# PROC099A_SOP_Headers_Reference.net
KiCad netlist of a schematic drawn in Altium Designer
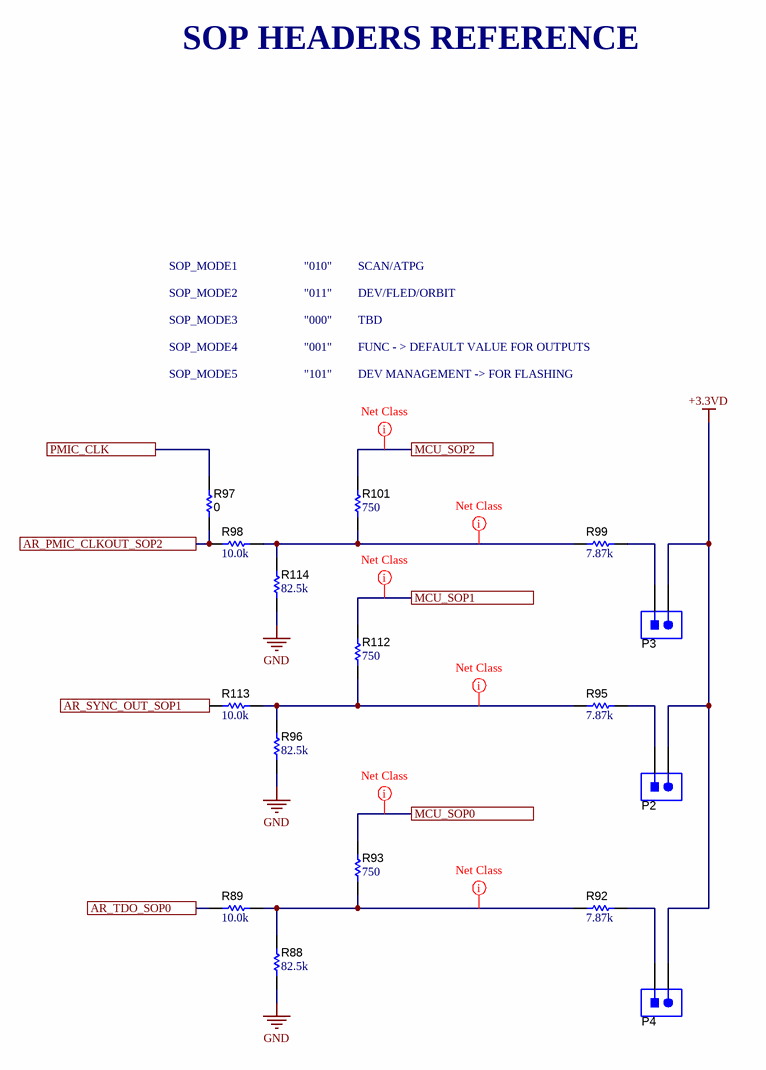
[diagram p0: PROC099A_SOP_Headers_Reference.SchDoc]

(export (version "E")
  (design (tool "Eeschema 10.0.6"))
  (components
    (comp (ref "P2")
      (value "TSW-102-07-G-S")
      (footprint "TSW-102-07-G-S")
      (description "Header, 100mil, 2x1, Gold, TH")
      (fields (field (name "MANUFACTURER") "Samtec"))
      (libsource (lib "Altium Vault - TI") (part "CMP-0075405-2"))
    )
    (comp (ref "P3")
      (value "TSW-102-07-G-S")
      (footprint "TSW-102-07-G-S")
      (description "Header, 100mil, 2x1, Gold, TH")
      (fields (field (name "MANUFACTURER") "Samtec"))
      (libsource (lib "Altium Vault - TI") (part "CMP-0075405-2"))
    )
    (comp (ref "P4")
      (value "TSW-102-07-G-S")
      (footprint "TSW-102-07-G-S")
      (description "Header, 100mil, 2x1, Gold, TH")
      (fields (field (name "MANUFACTURER") "Samtec"))
      (libsource (lib "Altium Vault - TI") (part "CMP-0075405-2"))
    )
    (comp (ref "R88")
      (value "CRCW040282K5FKED")
      (footprint "0402L")
      (description "RES, 82.5 k, 1%, 0.063 W, AEC-Q200 Grade 0, 0402")
      (fields (field (name "MANUFACTURER") "Vishay-Dale") (field (name "VALUEDISPLAYED") "82.5k"))
      (libsource (lib "Altium Vault - TI") (part "Resistor"))
    )
    (comp (ref "R89")
      (value "CRCW040210K0FKED")
      (footprint "0402L")
      (description "RES, 10.0 k, 1%, 0.063 W, AEC-Q200 Grade 0, 0402")
      (fields (field (name "MANUFACTURER") "Vishay-Dale") (field (name "VALUEDISPLAYED") "10.0k"))
      (libsource (lib "Altium Vault - TI") (part "CMP-0025958-3"))
    )
    (comp (ref "R92")
      (value "CRCW04027K87FKED")
      (footprint "0402L")
      (description "RES, 7.87 k, 1%, 0.063 W, AEC-Q200 Grade 0, 0402")
      (fields (field (name "MANUFACTURER") "Vishay-Dale") (field (name "VALUEDISPLAYED") "7.87k"))
      (libsource (lib "Altium Vault - TI") (part "Resistor"))
    )
    (comp (ref "R93")
      (value "CRCW0402750RFKED")
      (footprint "0402L")
      (description "RES, 750, 1%, 0.063 W, AEC-Q200 Grade 0, 0402")
      (fields (field (name "MANUFACTURER") "Vishay-Dale") (field (name "VALUEDISPLAYED") "750"))
      (libsource (lib "Altium Vault - TI") (part "Resistor"))
    )
    (comp (ref "R95")
      (value "CRCW04027K87FKED")
      (footprint "0402L")
      (description "RES, 7.87 k, 1%, 0.063 W, AEC-Q200 Grade 0, 0402")
      (fields (field (name "MANUFACTURER") "Vishay-Dale") (field (name "VALUEDISPLAYED") "7.87k"))
      (libsource (lib "Altium Vault - TI") (part "Resistor"))
    )
    (comp (ref "R96")
      (value "CRCW040282K5FKED")
      (footprint "0402L")
      (description "RES, 82.5 k, 1%, 0.063 W, AEC-Q200 Grade 0, 0402")
      (fields (field (name "MANUFACTURER") "Vishay-Dale") (field (name "VALUEDISPLAYED") "82.5k"))
      (libsource (lib "Altium Vault - TI") (part "Resistor"))
    )
    (comp (ref "R97")
      (value "ERJ-2GE0R00X")
      (footprint "0402L")
      (description "RES, 0, 5%, 0.063 W, 0402")
      (fields
        (field (name "MANUFACTURER") "Panasonic")
        (field (name "VALUEDISPLAYED") "0")
        (field (name "PUBLISHER") "Texas Instruments")
      )
      (libsource (lib "Altium Vault - TI") (part "CMP-0026992-2"))
    )
    (comp (ref "R98")
      (value "CRCW040210K0FKED")
      (footprint "0402L")
      (description "RES, 10.0 k, 1%, 0.063 W, AEC-Q200 Grade 0, 0402")
      (fields (field (name "MANUFACTURER") "Vishay-Dale") (field (name "VALUEDISPLAYED") "10.0k"))
      (libsource (lib "Altium Vault - TI") (part "CMP-0025958-3"))
    )
    (comp (ref "R99")
      (value "CRCW04027K87FKED")
      (footprint "0402L")
      (description "RES, 7.87 k, 1%, 0.063 W, AEC-Q200 Grade 0, 0402")
      (fields (field (name "MANUFACTURER") "Vishay-Dale") (field (name "VALUEDISPLAYED") "7.87k"))
      (libsource (lib "Altium Vault - TI") (part "Resistor"))
    )
    (comp (ref "R101")
      (value "CRCW0402750RFKED")
      (footprint "0402L")
      (description "RES, 750, 1%, 0.063 W, AEC-Q200 Grade 0, 0402")
      (fields (field (name "MANUFACTURER") "Vishay-Dale") (field (name "VALUEDISPLAYED") "750"))
      (libsource (lib "Altium Vault - TI") (part "CMP-0026542-2"))
    )
    (comp (ref "R112")
      (value "CRCW0402750RFKED")
      (footprint "0402L")
      (description "RES, 750, 1%, 0.063 W, AEC-Q200 Grade 0, 0402")
      (fields (field (name "MANUFACTURER") "Vishay-Dale") (field (name "VALUEDISPLAYED") "750"))
      (libsource (lib "Altium Vault - TI") (part "Resistor"))
    )
    (comp (ref "R113")
      (value "CRCW040210K0FKED")
      (footprint "0402L")
      (description "RES, 10.0 k, 1%, 0.063 W, AEC-Q200 Grade 0, 0402")
      (fields (field (name "MANUFACTURER") "Vishay-Dale") (field (name "VALUEDISPLAYED") "10.0k"))
      (libsource (lib "Altium Vault - TI") (part "CMP-0025958-3"))
    )
    (comp (ref "R114")
      (value "CRCW040282K5FKED")
      (footprint "0402L")
      (description "RES, 82.5 k, 1%, 0.063 W, AEC-Q200 Grade 0, 0402")
      (fields (field (name "MANUFACTURER") "Vishay-Dale") (field (name "VALUEDISPLAYED") "82.5k"))
      (libsource (lib "Altium Vault - TI") (part "CMP-0026574-2"))
    )
  )
  (nets
    (net (code "1") (name "+3.3VD") (class "Default")
      (node (ref "P2") (pin "2") (pinfunction "2_2") (pintype "passive"))
      (node (ref "P3") (pin "2") (pinfunction "2_2") (pintype "passive"))
      (node (ref "P4") (pin "2") (pinfunction "2_2") (pintype "passive"))
    )
    (net (code "2") (name "/AR_PMIC_CLKOUT_SOP2") (class "Default")
      (node (ref "R97") (pin "1") (pinfunction "1_1") (pintype "passive"))
      (node (ref "R98") (pin "1") (pinfunction "1_1") (pintype "passive"))
    )
    (net (code "3") (name "/AR_SYNC_OUT_SOP1") (class "Default")
      (node (ref "R113") (pin "1") (pinfunction "1_1") (pintype "passive"))
    )
    (net (code "4") (name "/AR_TDO_SOP0") (class "Default")
      (node (ref "R89") (pin "1") (pinfunction "1_1") (pintype "passive"))
    )
    (net (code "5") (name "/MCU_SOP0") (class "Default")
      (node (ref "R93") (pin "2") (pinfunction "2_2") (pintype "passive"))
    )
    (net (code "6") (name "/MCU_SOP1") (class "Default")
      (node (ref "R112") (pin "2") (pinfunction "2_2") (pintype "passive"))
    )
    (net (code "7") (name "/MCU_SOP2") (class "Default")
      (node (ref "R101") (pin "2") (pinfunction "2_2") (pintype "passive"))
    )
    (net (code "8") (name "/PMIC_CLK") (class "Default")
      (node (ref "R97") (pin "2") (pinfunction "2_2") (pintype "passive"))
    )
    (net (code "9") (name "GND") (class "Default")
      (node (ref "R114") (pin "1") (pinfunction "1_1") (pintype "passive"))
      (node (ref "R88") (pin "1") (pinfunction "1_1") (pintype "passive"))
      (node (ref "R96") (pin "1") (pinfunction "1_1") (pintype "passive"))
    )
    (net (code "10") (name "Net-(P2-Pad1)") (class "Default")
      (node (ref "P2") (pin "1") (pinfunction "1_1") (pintype "passive"))
      (node (ref "R95") (pin "2") (pinfunction "2_2") (pintype "passive"))
    )
    (net (code "11") (name "Net-(P3-Pad1)") (class "Default")
      (node (ref "P3") (pin "1") (pinfunction "1_1") (pintype "passive"))
      (node (ref "R99") (pin "2") (pinfunction "2_2") (pintype "passive"))
    )
    (net (code "12") (name "Net-(P4-Pad1)") (class "Default")
      (node (ref "P4") (pin "1") (pinfunction "1_1") (pintype "passive"))
      (node (ref "R92") (pin "2") (pinfunction "2_2") (pintype "passive"))
    )
    (net (code "13") (name "Net-(R88-Pad2)") (class "Default")
      (node (ref "R88") (pin "2") (pinfunction "2_2") (pintype "passive"))
      (node (ref "R89") (pin "2") (pinfunction "2_2") (pintype "passive"))
      (node (ref "R92") (pin "1") (pinfunction "1_1") (pintype "passive"))
      (node (ref "R93") (pin "1") (pinfunction "1_1") (pintype "passive"))
    )
    (net (code "14") (name "Net-(R101-Pad1)") (class "Default")
      (node (ref "R101") (pin "1") (pinfunction "1_1") (pintype "passive"))
      (node (ref "R114") (pin "2") (pinfunction "2_2") (pintype "passive"))
      (node (ref "R98") (pin "2") (pinfunction "2_2") (pintype "passive"))
      (node (ref "R99") (pin "1") (pinfunction "1_1") (pintype "passive"))
    )
    (net (code "15") (name "Net-(R112-Pad1)") (class "Default")
      (node (ref "R112") (pin "1") (pinfunction "1_1") (pintype "passive"))
      (node (ref "R113") (pin "2") (pinfunction "2_2") (pintype "passive"))
      (node (ref "R95") (pin "1") (pinfunction "1_1") (pintype "passive"))
      (node (ref "R96") (pin "2") (pinfunction "2_2") (pintype "passive"))
    )
  )
)
